# 3V3_Buck_For_Auton_LED.net
KiCad netlist of a schematic drawn in Altium Designer
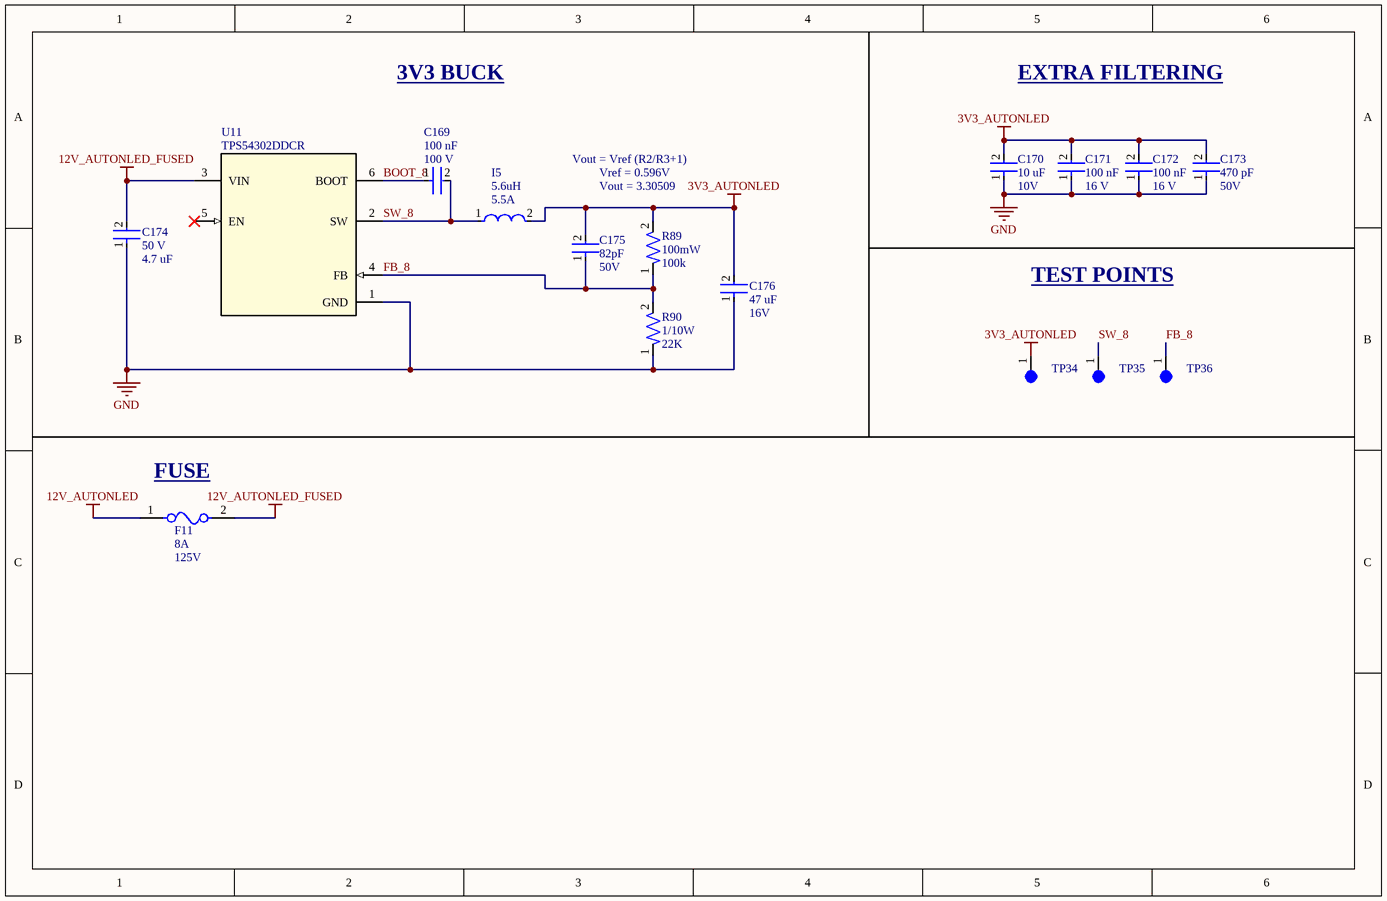
[diagram p0: 3V3_Buck_For_Auton_LED.SchDoc]

(export (version "E")
  (design (tool "Eeschema 10.0.6"))
  (components
    (comp (ref "C169")
      (value "CC0603KRX7R0BB104")
      (footprint "CAP-0603")
      (description "CAP CER 0.1UF 100V X7R 0603")
      (fields (field (name "CAPACITANCE") "100 nF") (field (name "VOLTAGE") "100 V"))
      (libsource (lib "JLC_25") (part "CAP-100N-0001"))
    )
    (comp (ref "C170")
      (value "CC0603KRX5R6BB106")
      (footprint "CAP-0603")
      (description "CAP CER 10UF 10V X5R 0603")
      (fields (field (name "VOLTAGE") "10V") (field (name "CAPACITANCE") "10 uF"))
      (libsource (lib "JLC_25") (part "CAP-10U-0001"))
    )
    (comp (ref "C171")
      (value "CC0402KRX7R7BB104")
      (footprint "CAP-0402")
      (description "CAP CER 0.1UF 16V X7R 0402")
      (fields (field (name "VOLTAGE RATING") "16 V") (field (name "CAPACITANCE") "100 nF"))
      (libsource (lib "JLC_25") (part "CAP-0.1U-0001"))
    )
    (comp (ref "C172")
      (value "CC0402KRX7R7BB104")
      (footprint "CAP-0402")
      (description "CAP CER 0.1UF 16V X7R 0402")
      (fields (field (name "VOLTAGE RATING") "16 V") (field (name "CAPACITANCE") "100 nF"))
      (libsource (lib "JLC_25") (part "CAP-0.1U-0001"))
    )
    (comp (ref "C173")
      (value "CC0805JRNPO9BN471")
      (footprint "CAP-0805")
      (description "CAP CER 470PF 50V C0G/NPO 0805")
      (fields (field (name "VOLTAGE") "50V") (field (name "CAPACITANCE") "470 pF"))
      (libsource (lib "JLC_25") (part "CAP-470P-0001"))
    )
    (comp (ref "C174")
      (value "CC0805KKX5R9BB475")
      (footprint "CAP-0805")
      (description "CAP CER 4.7UF 50V X5R 0805")
      (fields (field (name "VOLTAGE") "50 V") (field (name "CAPACITANCE") "4.7 uF"))
      (libsource (lib "JLC_25") (part "CAP-4.7U-0002"))
    )
    (comp (ref "C175")
      (value "CC0805JRNPO9BN820")
      (footprint "CAP-0805")
      (description "82 pF ±5% 50V Ceramic Capacitor C0G, NP0 0805 (2012 Metric)")
      (fields (field (name "VOLTAGE") "50V") (field (name "CAPACITANCE") "82pF"))
      (libsource (lib "JLC_25") (part "CAP-82P-0001"))
    )
    (comp (ref "C176")
      (value "GRM32ER61C476KE15L")
      (footprint "CAP-1210")
      (description "CAP CER 47UF 16V X5R 1210")
      (fields (field (name "CAPACITANCE") "47 uF") (field (name "VOLTAGE") "16V"))
      (libsource (lib "JLC_25") (part "CAP-47U-0002"))
    )
    (comp (ref "F11")
      (value "01550900M")
      (footprint "FUSE-0001")
      (description "FUSE BLOK CARTRIDGE 125V 10A SMD")
      (fields (field (name "FUSE CURRENT") "8A") (field (name "VOLTAGE RATING") "125V"))
      (libsource (lib "JLC_25") (part "FUSE-0001"))
    )
    (comp (ref "I5")
      (value "SRP6540-5R6M")
      (footprint "IND_SRP6540-5R6M")
      (description "FIXED IND 5.6UH 5.5A 38 MOHM SMD")
      (fields (field (name "SATURATION CURRENT") "5.5A") (field (name "INDUCTANCE") "5.6uH"))
      (libsource (lib "JLC_25") (part "IND-5.6U-0002"))
    )
    (comp (ref "R89")
      (value "RC0603FR-07100KL")
      (footprint "RES-0603")
      (description "RES SMD 100K OHM 1% 1/10W 0603")
      (fields
        (field (name "TOLERANCE") "1%")
        (field (name "POWER") "100mW")
        (field (name "RESISTANCE") "100k")
      )
      (libsource (lib "JLC_25") (part "RES-100k-0001"))
    )
    (comp (ref "R90")
      (value "RC0603FR-0722KL")
      (footprint "RES-0603")
      (description "22 kOhms ±1% 0.1W, 1/10W Chip Resistor 0603 (1608 Metric) Moisture Resistant Thick Film")
      (fields (field (name "POWER") "1/10W") (field (name "RESISTANCE") "22K"))
      (libsource (lib "JLC_25") (part "RES-22k-0001"))
    )
    (comp (ref "TP34")
      (value "5003")
      (footprint "TEST-POINT-0001")
      (description "Oranange PC Test Point, Miniature Phoisphor Bronze Silver Plating Through Hole Mounting Type")
      (libsource (lib "*") (part "TEST-POINT-0001"))
    )
    (comp (ref "TP35")
      (value "5003")
      (footprint "TEST-POINT-0001")
      (description "Oranange PC Test Point, Miniature Phoisphor Bronze Silver Plating Through Hole Mounting Type")
      (libsource (lib "*") (part "TEST-POINT-0001"))
    )
    (comp (ref "TP36")
      (value "5003")
      (footprint "TEST-POINT-0001")
      (description "Oranange PC Test Point, Miniature Phoisphor Bronze Silver Plating Through Hole Mounting Type")
      (libsource (lib "*") (part "TEST-POINT-0001"))
    )
    (comp (ref "U11")
      (value "TPS54302DDCR")
      (footprint "IC-SOT-23-6")
      (description "IC REG BUCK ADJ 3A SOT23")
      (libsource (lib "JLC_25") (part "IC-BUCK-0004"))
    )
  )
  (nets
    (net (code "1") (name "/BOOT_8") (class "Default")
      (node (ref "C169") (pin "1") (pinfunction "1_1") (pintype "passive"))
      (node (ref "U11") (pin "6") (pinfunction "BOOT_6") (pintype "power_in"))
    )
    (net (code "2") (name "/FB_8") (class "Default")
      (node (ref "C175") (pin "1") (pinfunction "1_1") (pintype "passive"))
      (node (ref "R89") (pin "1") (pinfunction "1_1") (pintype "passive"))
      (node (ref "R90") (pin "2") (pinfunction "2_2") (pintype "passive"))
      (node (ref "TP36") (pin "1") (pinfunction "0_1") (pintype "passive"))
      (node (ref "U11") (pin "4") (pinfunction "FB_4") (pintype "input"))
    )
    (net (code "3") (name "/SW_8") (class "Default")
      (node (ref "C169") (pin "2") (pinfunction "2_2") (pintype "passive"))
      (node (ref "I5") (pin "1") (pinfunction "1_1") (pintype "passive"))
      (node (ref "TP35") (pin "1") (pinfunction "0_1") (pintype "passive"))
      (node (ref "U11") (pin "2") (pinfunction "SW_2") (pintype "power_in"))
    )
    (net (code "4") (name "3V3_AUTONLED") (class "Default")
      (node (ref "C170") (pin "2") (pinfunction "2_2") (pintype "passive"))
      (node (ref "C171") (pin "2") (pinfunction "2_2") (pintype "passive"))
      (node (ref "C172") (pin "2") (pinfunction "2_2") (pintype "passive"))
      (node (ref "C173") (pin "2") (pinfunction "2_2") (pintype "passive"))
      (node (ref "C175") (pin "2") (pinfunction "2_2") (pintype "passive"))
      (node (ref "C176") (pin "2") (pinfunction "2_2") (pintype "passive"))
      (node (ref "I5") (pin "2") (pinfunction "2_2") (pintype "passive"))
      (node (ref "R89") (pin "2") (pinfunction "2_2") (pintype "passive"))
      (node (ref "TP34") (pin "1") (pinfunction "0_1") (pintype "passive"))
    )
    (net (code "5") (name "12V_AUTONLED") (class "Default")
      (node (ref "F11") (pin "1") (pinfunction "1_1") (pintype "passive"))
    )
    (net (code "6") (name "12V_AUTONLED_FUSED") (class "Default")
      (node (ref "C174") (pin "2") (pinfunction "2_2") (pintype "passive"))
      (node (ref "F11") (pin "2") (pinfunction "2_2") (pintype "passive"))
      (node (ref "U11") (pin "3") (pinfunction "VIN_3") (pintype "power_in"))
    )
    (net (code "7") (name "GND") (class "Default")
      (node (ref "C170") (pin "1") (pinfunction "1_1") (pintype "passive"))
      (node (ref "C171") (pin "1") (pinfunction "1_1") (pintype "passive"))
      (node (ref "C172") (pin "1") (pinfunction "1_1") (pintype "passive"))
      (node (ref "C173") (pin "1") (pinfunction "1_1") (pintype "passive"))
      (node (ref "C174") (pin "1") (pinfunction "1_1") (pintype "passive"))
      (node (ref "C176") (pin "1") (pinfunction "1_1") (pintype "passive"))
      (node (ref "R90") (pin "1") (pinfunction "1_1") (pintype "passive"))
      (node (ref "U11") (pin "1") (pinfunction "GND_1") (pintype "power_in"))
    )
    (net (code "8") (name "unconnected-(U11-EN-Pad5)") (class "Default")
      (node (ref "U11") (pin "5") (pinfunction "EN_5") (pintype "input+no_connect"))
    )
  )
)
